# USB_SWITCH.net
KiCad netlist of a schematic drawn in Altium Designer
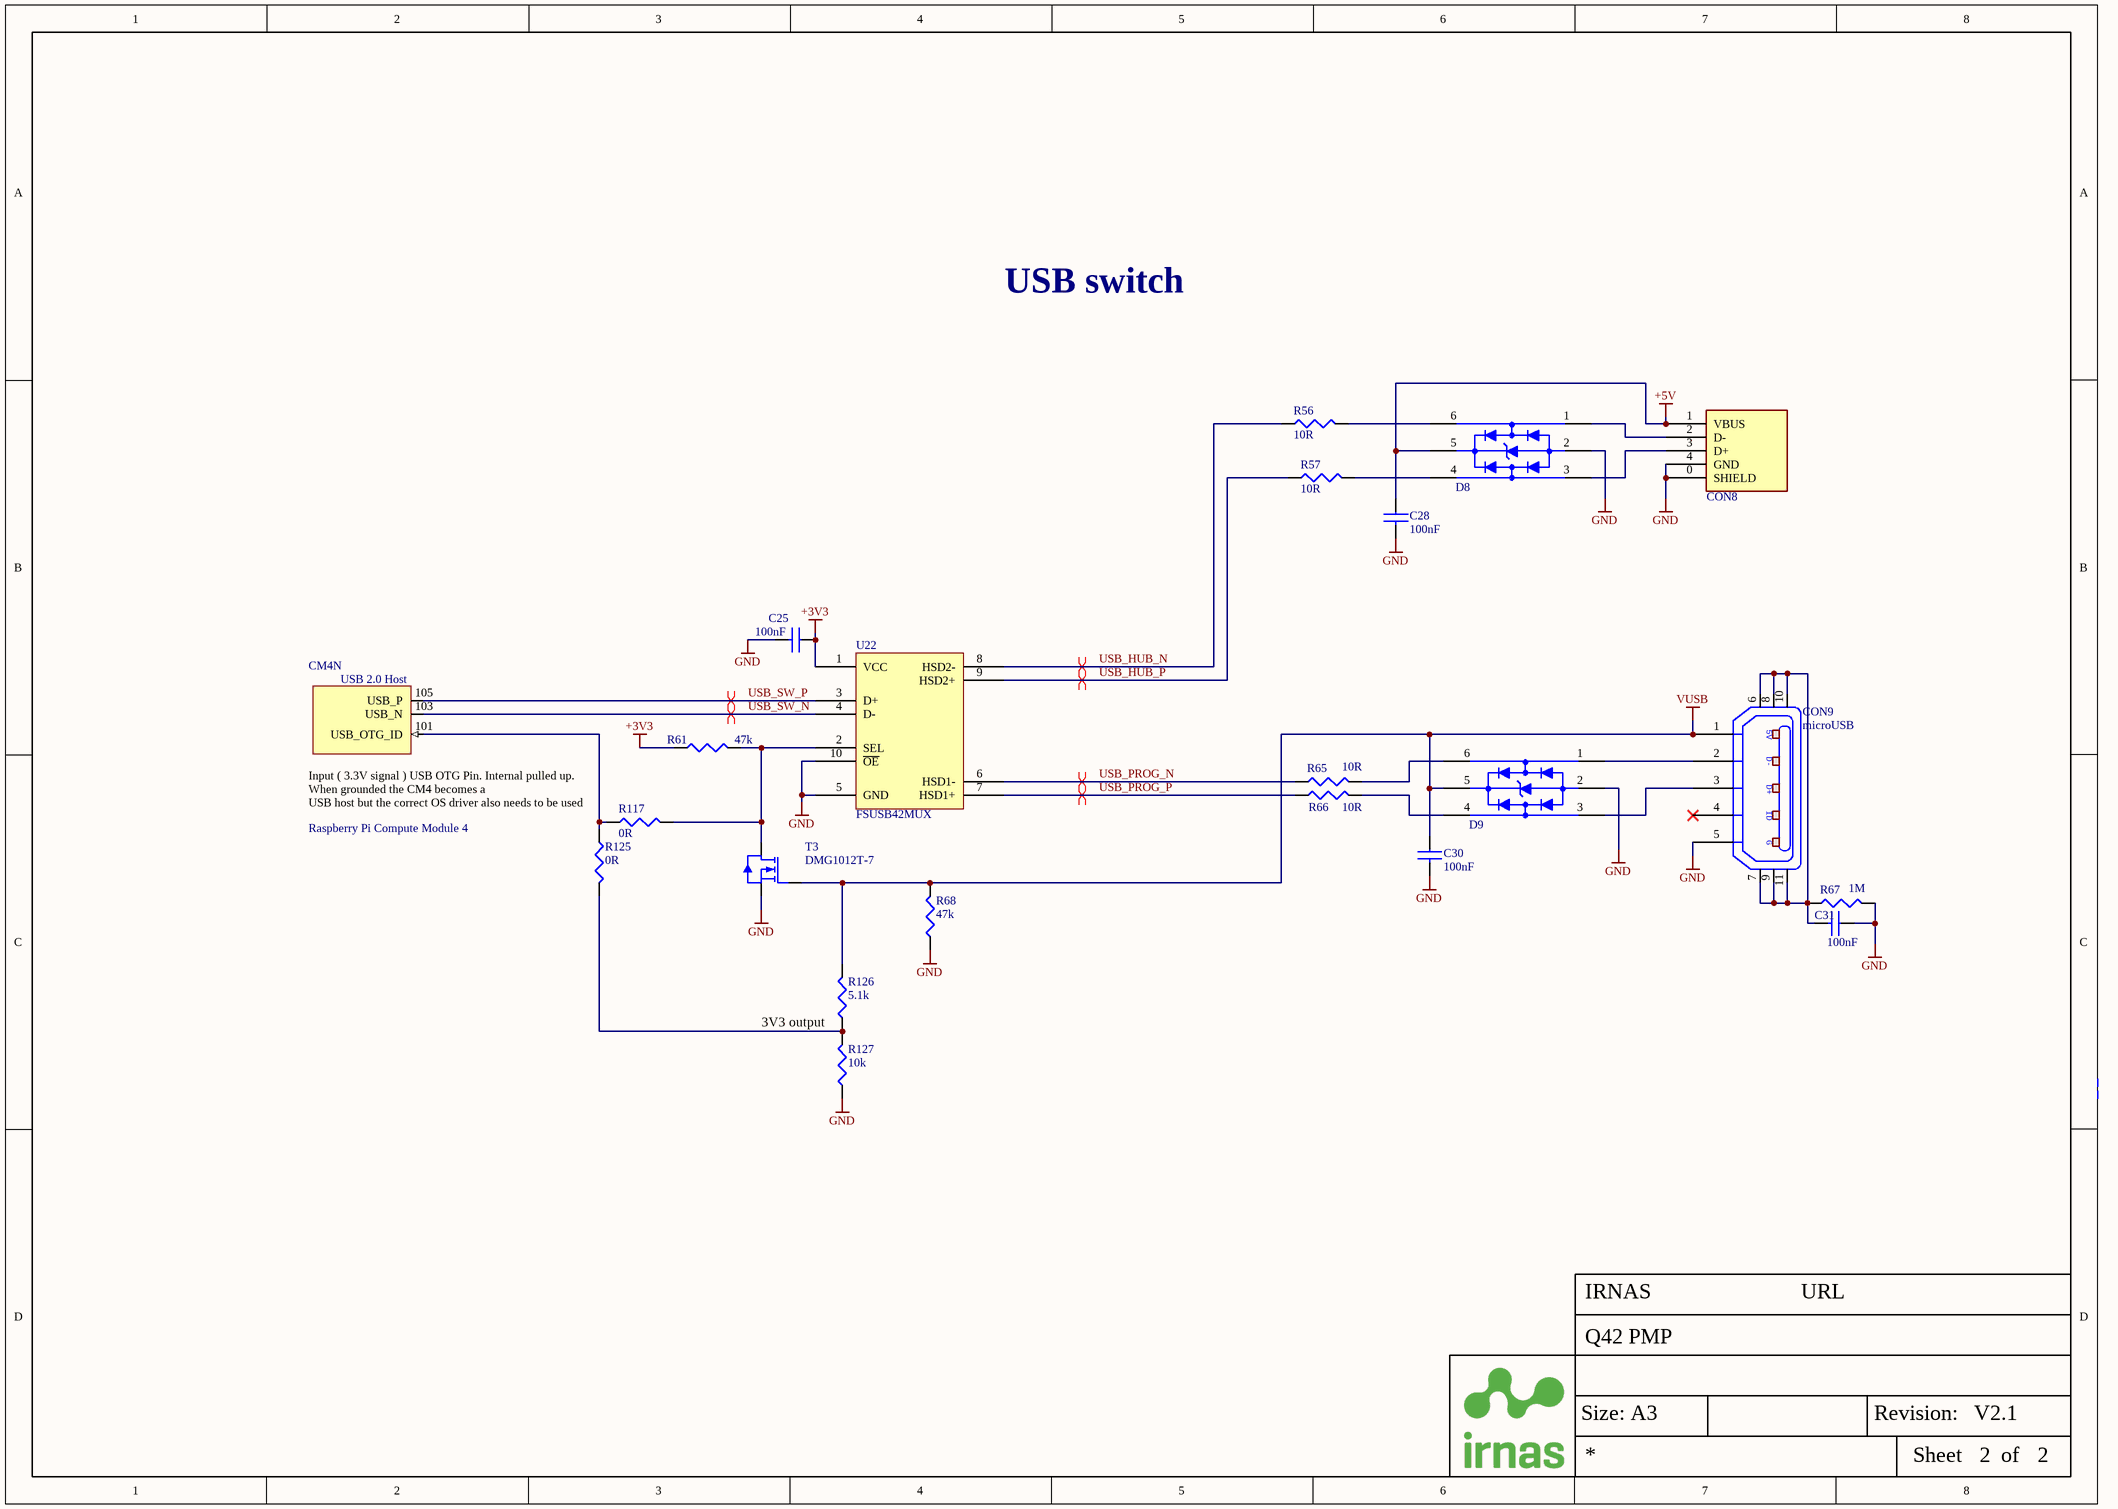
[diagram p0: USB SWITCH.SchDoc]

(export (version "E")
  (design (tool "Eeschema 10.0.6"))
  (components
    (comp (ref "C25")
      (value "100nF")
      (footprint "CAP0603")
      (description "MURATA - GRM188R71C104KA01J - CAP, MLCC, X7R, 0.1UF, 16V, 0603")
      (fields
        (field (name "MANUFACTURER") "MURATA")
        (field (name "MANUFACTURER PART NUMBER") "GRM188R71C104KA01J")
      )
      (libsource (lib "SCHLib") (part "100nF"))
    )
    (comp (ref "C28")
      (value "100nF")
      (footprint "CAP0603")
      (description "MURATA - GRM188R71C104KA01J - CAP, MLCC, X7R, 0.1UF, 16V, 0603")
      (fields
        (field (name "MANUFACTURER") "MURATA")
        (field (name "MANUFACTURER PART NUMBER") "GRM188R71C104KA01J")
      )
      (libsource (lib "Passive") (part "C - 100nF"))
    )
    (comp (ref "C30")
      (value "100nF")
      (footprint "CAP0603")
      (description "MURATA - GRM188R71C104KA01J - CAP, MLCC, X7R, 0.1UF, 16V, 0603")
      (fields
        (field (name "MANUFACTURER") "MURATA")
        (field (name "MANUFACTURER PART NUMBER") "GRM188R71C104KA01J")
      )
      (libsource (lib "Passive") (part "C - 100nF"))
    )
    (comp (ref "C31")
      (value "100nF")
      (footprint "CAP0603")
      (description "MURATA - GRM188R71C104KA01J - CAP, MLCC, X7R, 0.1UF, 16V, 0603")
      (fields
        (field (name "MANUFACTURER") "MURATA")
        (field (name "MANUFACTURER PART NUMBER") "GRM188R71C104KA01J")
      )
      (libsource (lib "Passive") (part "C - 100nF"))
    )
    (comp (ref "CM4")
      (value "Raspberry Pi Compute Module 4")
      (footprint "Raspberry pi CM4")
      (description "Raspberry Pi Compute Module 4 (! order 2 connectors !)")
      (libsource (lib "Connectors") (part "CM4"))
    )
    (comp (ref "CON8")
      (value "629104190121")
      (footprint "WE-629104190121")
      (description "USB Connector, USB Type A, USB 2.0, Receptacle, 4 Ways, Surface Mount, Horizontal")
      (fields (field (name "PART NUMBER") "691305130004") (field (name "PUBLISHER") "Wurth Elektronik"))
      (libsource (lib "Connectors") (part "WR-USB2.0-629104190121"))
    )
    (comp (ref "CON9")
      (value "microUSB")
      (footprint "microUSB-CHINA")
      (libsource (lib "Connectors") (part "Micro USB CHINA 1"))
    )
    (comp (ref "D8")
      (value "USBLC6-2SC6")
      (footprint "SOT23-6")
      (description "ESD Protection Device, 17 V, SOT-23, 6 Pins, 6 V, 85 W, USBLC Series")
      (libsource (lib "Active") (part "D_ESD - USBLC6-2SC6"))
    )
    (comp (ref "D9")
      (value "USBLC6-2SC6")
      (footprint "SOT23-6")
      (description "ESD Protection Device, 17 V, SOT-23, 6 Pins, 6 V, 85 W, USBLC Series")
      (libsource (lib "Active") (part "D_ESD - USBLC6-2SC6"))
    )
    (comp (ref "R56")
      (value "10R")
      (footprint "RES0603")
      (description "VISHAY - RCA060310R0FKEA - RES, AUTO, THICK FILM, 10R, 1%, 0603")
      (fields
        (field (name "MANUFACTURER") "VISHAY")
        (field (name "MANUFACTURER PART NUMBER") "RCA060310R0FKEA")
      )
      (libsource (lib "Passive") (part "R - 10R"))
    )
    (comp (ref "R57")
      (value "10R")
      (footprint "RES0603")
      (description "VISHAY - RCA060310R0FKEA - RES, AUTO, THICK FILM, 10R, 1%, 0603")
      (fields
        (field (name "MANUFACTURER") "VISHAY")
        (field (name "MANUFACTURER PART NUMBER") "RCA060310R0FKEA")
      )
      (libsource (lib "Passive") (part "R - 10R"))
    )
    (comp (ref "R61")
      (value "47k")
      (footprint "RES0603")
      (description "MULTICOMP - MCMR06X4702FTL - RES, CERAMIC, 47K, 1%, 0.1W, 0603")
      (fields
        (field (name "MANUFACTURER") "MULTICOMP")
        (field (name "MANUFACTURER PART NUMBER") "MCMR06X4702FTL")
      )
      (libsource (lib "SCHLib") (part "MCMR06X4702FTL"))
    )
    (comp (ref "R65")
      (value "10R")
      (footprint "RES0603")
      (description "VISHAY - RCA060310R0FKEA - RES, AUTO, THICK FILM, 10R, 1%, 0603")
      (fields
        (field (name "MANUFACTURER") "VISHAY")
        (field (name "MANUFACTURER PART NUMBER") "RCA060310R0FKEA")
      )
      (libsource (lib "Passive") (part "R - 10R"))
    )
    (comp (ref "R66")
      (value "10R")
      (footprint "RES0603")
      (description "VISHAY - RCA060310R0FKEA - RES, AUTO, THICK FILM, 10R, 1%, 0603")
      (fields
        (field (name "MANUFACTURER") "VISHAY")
        (field (name "MANUFACTURER PART NUMBER") "RCA060310R0FKEA")
      )
      (libsource (lib "Passive") (part "R - 10R"))
    )
    (comp (ref "R67")
      (value "1M")
      (footprint "RES0603")
      (description "MULTICOMP - MC0063W060311M - RES, THICK FILM, 1M, 1%, 0.063W, 0603")
      (fields
        (field (name "MANUFACTURER") "MULTICOMP")
        (field (name "MANUFACTURER PART NUMBER") "MC0063W060311M")
      )
      (libsource (lib "Passive") (part "R - 1M"))
    )
    (comp (ref "R68")
      (value "47k")
      (footprint "RES0603")
      (description "MULTICOMP - MCMR06X4702FTL - RES, CERAMIC, 47K, 1%, 0.1W, 0603")
      (fields
        (field (name "MANUFACTURER") "MULTICOMP")
        (field (name "MANUFACTURER PART NUMBER") "MCMR06X4702FTL")
      )
      (libsource (lib "SCHLib") (part "MCMR06X4702FTL"))
    )
    (comp (ref "R117")
      (value "0R")
      (footprint "RES0603")
      (description "BOURNS - CR0603-J/-000ELF - RES, THICK FILM, 0R, 5%, 0.1W, 0603")
      (fields
        (field (name "MANUFACTURER") "BOURNS")
        (field (name "MANUFACTURER PART NUMBER") "CR0603-J/-000ELF")
      )
      (libsource (lib "Passive") (part "R - 0R"))
    )
    (comp (ref "R125")
      (value "0R")
      (footprint "RES0603")
      (description "BOURNS - CR0603-J/-000ELF - RES, THICK FILM, 0R, 5%, 0.1W, 0603")
      (fields
        (field (name "MANUFACTURER") "BOURNS")
        (field (name "MANUFACTURER PART NUMBER") "CR0603-J/-000ELF")
      )
      (libsource (lib "Passive") (part "R - 0R"))
    )
    (comp (ref "R126")
      (value "5.1k")
      (footprint "RES0603")
      (description "SMD Chip Resistor, 5.1 kohm, ± 1%, 100 mW, 0603 [1608 Metric], Thick Film, General Purpose")
      (libsource (lib "Passive") (part "R - 5.1k"))
    )
    (comp (ref "R127")
      (value "10k")
      (footprint "RES0603")
      (description "MULTICOMP - MCMR06X103 JTL - RES, CERAMIC, 10K, 5%, 0.1W, 0603")
      (fields
        (field (name "MANUFACTURER") "MULTICOMP")
        (field (name "MANUFACTURER PART NUMBER") "MCMR06X103 JTL")
      )
      (libsource (lib "Passive") (part "R - 10k"))
    )
    (comp (ref "T3")
      (value "DMG1012T-7")
      (footprint "SOT-523")
      (description "Power MOSFET, N Channel, 20 V, 630 mA, 0.3 ohm, SOT-523, Surface Mount")
      (libsource (lib "Active") (part "T_M - DMG1012T-7"))
    )
    (comp (ref "U22")
      (value "FSUSB42MUX")
      (footprint "MSOP-10")
      (description "Analogue Switch, UART, 2 Channels, DPDT, 4.5 ohm, 2.4V to 3.6V, MSOP, 10 Pins")
      (libsource (lib "Active") (part "SW - FSUSB42MUX"))
    )
  )
  (nets
    (net (code "1") (name "+3V3") (class "Default")
      (node (ref "C25") (pin "1") (pinfunction "1_1") (pintype "passive"))
      (node (ref "R61") (pin "1") (pinfunction "1_1") (pintype "passive"))
      (node (ref "U22") (pin "1") (pinfunction "VCC_1") (pintype "passive"))
    )
    (net (code "2") (name "+5V") (class "Default")
      (node (ref "C28") (pin "1") (pinfunction "1_1") (pintype "passive"))
      (node (ref "CON8") (pin "1") (pinfunction "VBUS_1") (pintype "passive"))
      (node (ref "D8") (pin "5") (pinfunction "5_5") (pintype "passive"))
    )
    (net (code "3") (name "/USB_HUB_N") (class "Default")
      (node (ref "R56") (pin "1") (pinfunction "1_1") (pintype "passive"))
      (node (ref "U22") (pin "8") (pinfunction "HSD2-_8") (pintype "passive"))
    )
    (net (code "4") (name "/USB_HUB_P") (class "Default")
      (node (ref "R57") (pin "1") (pinfunction "1_1") (pintype "passive"))
      (node (ref "U22") (pin "9") (pinfunction "HSD2+_9") (pintype "passive"))
    )
    (net (code "5") (name "/USB_PROG_N") (class "Default")
      (node (ref "R65") (pin "1") (pinfunction "1_1") (pintype "passive"))
      (node (ref "U22") (pin "6") (pinfunction "HSD1-_6") (pintype "passive"))
    )
    (net (code "6") (name "/USB_PROG_P") (class "Default")
      (node (ref "R66") (pin "1") (pinfunction "1_1") (pintype "passive"))
      (node (ref "U22") (pin "7") (pinfunction "HSD1+_7") (pintype "passive"))
    )
    (net (code "7") (name "/USB_SW_N") (class "Default")
      (node (ref "CM4") (pin "103") (pinfunction "USB_N_103") (pintype "passive"))
      (node (ref "U22") (pin "4") (pinfunction "D-_4") (pintype "passive"))
    )
    (net (code "8") (name "/USB_SW_P") (class "Default")
      (node (ref "CM4") (pin "105") (pinfunction "USB_P_105") (pintype "passive"))
      (node (ref "U22") (pin "3") (pinfunction "D+_3") (pintype "passive"))
    )
    (net (code "9") (name "GND") (class "Default")
      (node (ref "C25") (pin "2") (pinfunction "2_2") (pintype "passive"))
      (node (ref "C28") (pin "2") (pinfunction "2_2") (pintype "passive"))
      (node (ref "C30") (pin "2") (pinfunction "2_2") (pintype "passive"))
      (node (ref "C31") (pin "1") (pinfunction "1_1") (pintype "passive"))
      (node (ref "CON8") (pin "0") (pinfunction "SHIELD_0") (pintype "passive"))
      (node (ref "CON8") (pin "4") (pinfunction "GND_4") (pintype "passive"))
      (node (ref "CON9") (pin "5") (pinfunction "P5_5") (pintype "passive"))
      (node (ref "D8") (pin "2") (pinfunction "2_2") (pintype "passive"))
      (node (ref "D9") (pin "2") (pinfunction "2_2") (pintype "passive"))
      (node (ref "R127") (pin "1") (pinfunction "1_1") (pintype "passive"))
      (node (ref "R67") (pin "2") (pinfunction "2_2") (pintype "passive"))
      (node (ref "R68") (pin "1") (pinfunction "1_1") (pintype "passive"))
      (node (ref "T3") (pin "2") (pinfunction "S_2") (pintype "passive"))
      (node (ref "U22") (pin "10") (pinfunction "~{OE}_10") (pintype "passive"))
      (node (ref "U22") (pin "5") (pinfunction "GND_5") (pintype "passive"))
    )
    (net (code "10") (name "Net-(C31-Pad2)") (class "Default")
      (node (ref "C31") (pin "2") (pinfunction "2_2") (pintype "passive"))
      (node (ref "CON9") (pin "10") (pinfunction "10_10") (pintype "passive"))
      (node (ref "CON9") (pin "11") (pinfunction "11_11") (pintype "passive"))
      (node (ref "CON9") (pin "6") (pinfunction "6_6") (pintype "passive"))
      (node (ref "CON9") (pin "7") (pinfunction "7_7") (pintype "passive"))
      (node (ref "CON9") (pin "8") (pinfunction "8_8") (pintype "passive"))
      (node (ref "CON9") (pin "9") (pinfunction "9_9") (pintype "passive"))
      (node (ref "R67") (pin "1") (pinfunction "1_1") (pintype "passive"))
    )
    (net (code "11") (name "Net-(CM4N-USB_OTG_ID)") (class "Default")
      (node (ref "CM4") (pin "101") (pinfunction "USB_OTG_ID_101") (pintype "input"))
      (node (ref "R117") (pin "1") (pinfunction "1_1") (pintype "passive"))
      (node (ref "R125") (pin "1") (pinfunction "1_1") (pintype "passive"))
    )
    (net (code "12") (name "Net-(CON8-D+)") (class "Default")
      (node (ref "CON8") (pin "3") (pinfunction "D+_3") (pintype "passive"))
      (node (ref "D8") (pin "3") (pinfunction "3_3") (pintype "passive"))
    )
    (net (code "13") (name "Net-(CON8-D-)") (class "Default")
      (node (ref "CON8") (pin "2") (pinfunction "D-_2") (pintype "passive"))
      (node (ref "D8") (pin "1") (pinfunction "1_1") (pintype "passive"))
    )
    (net (code "14") (name "Net-(CON9-P2)") (class "Default")
      (node (ref "CON9") (pin "2") (pinfunction "P2_2") (pintype "passive"))
      (node (ref "D9") (pin "1") (pinfunction "1_1") (pintype "passive"))
    )
    (net (code "15") (name "Net-(CON9-P3)") (class "Default")
      (node (ref "CON9") (pin "3") (pinfunction "P3_3") (pintype "passive"))
      (node (ref "D9") (pin "3") (pinfunction "3_3") (pintype "passive"))
    )
    (net (code "16") (name "Net-(D8-Pad4)") (class "Default")
      (node (ref "D8") (pin "4") (pinfunction "4_4") (pintype "passive"))
      (node (ref "R57") (pin "2") (pinfunction "2_2") (pintype "passive"))
    )
    (net (code "17") (name "Net-(D8-Pad6)") (class "Default")
      (node (ref "D8") (pin "6") (pinfunction "6_6") (pintype "passive"))
      (node (ref "R56") (pin "2") (pinfunction "2_2") (pintype "passive"))
    )
    (net (code "18") (name "Net-(D9-Pad4)") (class "Default")
      (node (ref "D9") (pin "4") (pinfunction "4_4") (pintype "passive"))
      (node (ref "R66") (pin "2") (pinfunction "2_2") (pintype "passive"))
    )
    (net (code "19") (name "Net-(D9-Pad6)") (class "Default")
      (node (ref "D9") (pin "6") (pinfunction "6_6") (pintype "passive"))
      (node (ref "R65") (pin "2") (pinfunction "2_2") (pintype "passive"))
    )
    (net (code "20") (name "Net-(R125-Pad2)") (class "Default")
      (node (ref "R125") (pin "2") (pinfunction "2_2") (pintype "passive"))
      (node (ref "R126") (pin "1") (pinfunction "1_1") (pintype "passive"))
      (node (ref "R127") (pin "2") (pinfunction "2_2") (pintype "passive"))
    )
    (net (code "21") (name "Net-(T3-D)") (class "Default")
      (node (ref "R117") (pin "2") (pinfunction "2_2") (pintype "passive"))
      (node (ref "R61") (pin "2") (pinfunction "2_2") (pintype "passive"))
      (node (ref "T3") (pin "3") (pinfunction "D_3") (pintype "passive"))
      (node (ref "U22") (pin "2") (pinfunction "SEL_2") (pintype "passive"))
    )
    (net (code "22") (name "VUSB") (class "Default")
      (node (ref "C30") (pin "1") (pinfunction "1_1") (pintype "passive"))
      (node (ref "CON9") (pin "1") (pinfunction "P1_1") (pintype "passive"))
      (node (ref "D9") (pin "5") (pinfunction "5_5") (pintype "passive"))
      (node (ref "R126") (pin "2") (pinfunction "2_2") (pintype "passive"))
      (node (ref "R68") (pin "2") (pinfunction "2_2") (pintype "passive"))
      (node (ref "T3") (pin "1") (pinfunction "G_1") (pintype "passive"))
    )
    (net (code "23") (name "unconnected-(CON9-P4-Pad4)") (class "Default")
      (node (ref "CON9") (pin "4") (pinfunction "P4_4") (pintype "passive+no_connect"))
    )
  )
)
